# pj9.net
KiCad netlist of a schematic drawn in EAGLE
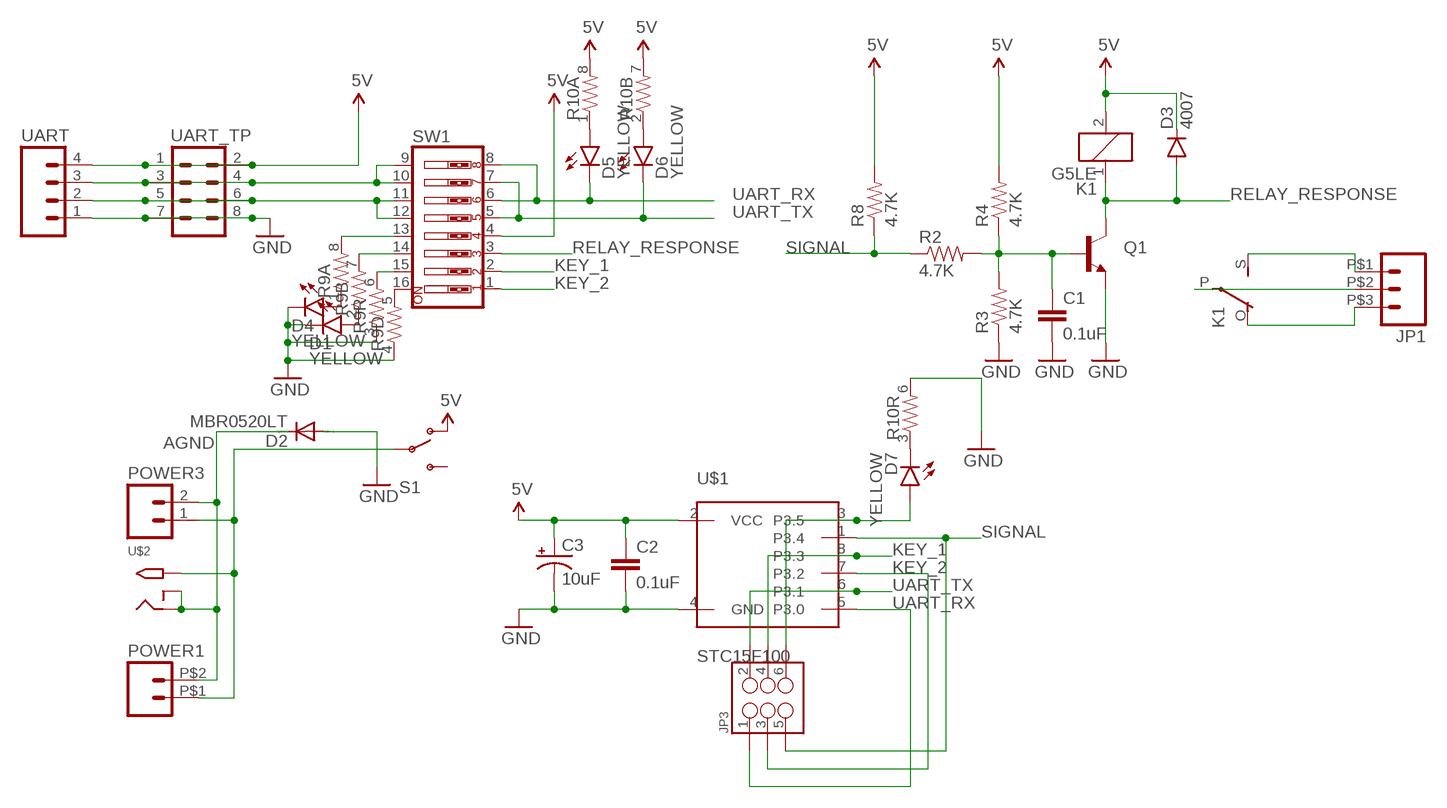
[diagram p0: schematic, sheet 1]

(export (version "E")
  (design (tool "Eeschema 10.0.6"))
  (components
    (comp (ref "C1")
      (value "0.1uF")
      (footprint "eagle-import:0603-CAP")
      (libsource (lib "eagle-import") (part "0.1UF-25V(+80/-20%)(0603)"))
    )
    (comp (ref "C2")
      (value "0.1uF")
      (footprint "eagle-import:0603-CAP")
      (libsource (lib "eagle-import") (part "0.1UF-25V(+80/-20%)(0603)"))
    )
    (comp (ref "C3")
      (value "10uF")
      (footprint "eagle-import:EIA3216")
      (libsource (lib "eagle-import") (part "10UF-16V-10%(TANT)"))
    )
    (comp (ref "D1")
      (value "YELLOW")
      (footprint "eagle-import:LED-1206")
      (libsource (lib "eagle-import") (part "LED-YELLOW1206"))
    )
    (comp (ref "D2")
      (value "MBR0520LT")
      (footprint "eagle-import:SOD123")
      (libsource (lib "eagle-import") (part "MBR0520LT"))
    )
    (comp (ref "D3")
      (value "4007")
      (footprint "eagle-import:SMA-DIODE_ALT")
      (libsource (lib "eagle-import") (part "DIODESMA-ALT"))
    )
    (comp (ref "D4")
      (value "YELLOW")
      (footprint "eagle-import:LED-1206")
      (libsource (lib "eagle-import") (part "LED-YELLOW1206"))
    )
    (comp (ref "D5")
      (value "YELLOW")
      (footprint "eagle-import:LED-1206")
      (libsource (lib "eagle-import") (part "LED-YELLOW1206"))
    )
    (comp (ref "D6")
      (value "YELLOW")
      (footprint "eagle-import:LED-1206")
      (libsource (lib "eagle-import") (part "LED-YELLOW1206"))
    )
    (comp (ref "D7")
      (value "YELLOW")
      (footprint "eagle-import:LED-1206")
      (libsource (lib "eagle-import") (part "LED-YELLOW1206"))
    )
    (comp (ref "JP1")
      (value "M035.08")
      (footprint "eagle-import:1X03_5.08")
      (libsource (lib "eagle-import") (part "M035.08"))
    )
    (comp (ref "JP3")
      (value "M03X2")
      (footprint "eagle-import:2X3_SMD")
      (libsource (lib "eagle-import") (part "M03X2"))
    )
    (comp (ref "K1")
      (value "G5LE")
      (footprint "eagle-import:G5LE")
      (libsource (lib "eagle-import") (part "G5LE"))
    )
    (comp (ref "POWER1")
      (value "M02")
      (footprint "eagle-import:1X02_5.08")
      (libsource (lib "eagle-import") (part "M02"))
    )
    (comp (ref "POWER3")
      (value "M02LOCK")
      (footprint "eagle-import:1X02_LOCK")
      (libsource (lib "eagle-import") (part "M02LOCK"))
    )
    (comp (ref "Q1")
      (value "TRANSISTOR_NPNSOT23-3")
      (footprint "eagle-import:SOT23-3")
      (libsource (lib "eagle-import") (part "TRANSISTOR_NPNSOT23-3"))
    )
    (comp (ref "R2")
      (value "4.7K")
      (footprint "eagle-import:0603-RES")
      (libsource (lib "eagle-import") (part "470OHM1/10W1%(0603)"))
    )
    (comp (ref "R3")
      (value "4.7K")
      (footprint "eagle-import:0603-RES")
      (libsource (lib "eagle-import") (part "470OHM1/10W1%(0603)"))
    )
    (comp (ref "R4")
      (value "4.7K")
      (footprint "eagle-import:0603-RES")
      (libsource (lib "eagle-import") (part "470OHM1/10W1%(0603)"))
    )
    (comp (ref "R8")
      (value "4.7K")
      (footprint "eagle-import:0603-RES")
      (libsource (lib "eagle-import") (part "470OHM1/10W1%(0603)"))
    )
    (comp (ref "R9")
      (value "RESISTOR-ARRAY0603-ARV")
      (footprint "eagle-import:0603-ARV")
      (libsource (lib "eagle-import") (part "RESISTOR-ARRAY0603-ARV"))
    )
    (comp (ref "R10")
      (value "RESISTOR-ARRAY0603-ARV")
      (footprint "eagle-import:0603-ARV")
      (libsource (lib "eagle-import") (part "RESISTOR-ARRAY0603-ARV"))
    )
    (comp (ref "S1")
      (value "SWITCH-SPDTSMD")
      (footprint "eagle-import:AYZ0202")
      (libsource (lib "eagle-import") (part "SWITCH-SPDTSMD"))
    )
    (comp (ref "SW1")
      (value "SW_DIP-8-SMT-HALFSIZE")
      (footprint "eagle-import:DIPSWITCH-08-50MIL")
      (libsource (lib "eagle-import") (part "SW_DIP-8-SMT-HALFSIZE"))
    )
    (comp (ref "U$1")
      (value "STC15F100")
      (footprint "eagle-import:SO08-TIGHT")
      (libsource (lib "eagle-import") (part "STC15F100"))
    )
    (comp (ref "U$2")
      (value "2.1MMJACK")
      (footprint "eagle-import:PJ-102A")
      (libsource (lib "eagle-import") (part "2.1MMJACK"))
    )
    (comp (ref "UART")
      (value "M04LOCK")
      (footprint "eagle-import:1X04_LOCK")
      (libsource (lib "eagle-import") (part "M04LOCK"))
    )
    (comp (ref "UART_TP")
      (value "M04X2SMD")
      (footprint "eagle-import:2X4_SMD")
      (libsource (lib "eagle-import") (part "M04X2SMD"))
    )
  )
  (nets
    (net (code "1") (name "/AGND") (class "Default")
      (node (ref "D2") (pin "C") (pinfunction "C_C") (pintype "passive"))
      (node (ref "POWER1") (pin "P$2") (pinfunction "2_P$2") (pintype "passive"))
      (node (ref "POWER3") (pin "2") (pinfunction "2_2") (pintype "passive"))
      (node (ref "U$2") (pin "RING") (pinfunction "RING_RING") (pintype "bidirectional"))
      (node (ref "U$2") (pin "RING_SW") (pinfunction "RING_SW_RING_SW") (pintype "bidirectional"))
    )
    (net (code "2") (name "/KEY_1") (class "Default")
      (node (ref "JP3") (pin "4") (pinfunction "4_4") (pintype "bidirectional"))
      (node (ref "SW1") (pin "2") (pinfunction "2_2") (pintype "passive"))
      (node (ref "U$1") (pin "8") (pinfunction "P3.3_8") (pintype "bidirectional"))
    )
    (net (code "3") (name "/KEY_2") (class "Default")
      (node (ref "JP3") (pin "3") (pinfunction "3_3") (pintype "bidirectional"))
      (node (ref "SW1") (pin "1") (pinfunction "1_1") (pintype "passive"))
      (node (ref "U$1") (pin "7") (pinfunction "P3.2_7") (pintype "bidirectional"))
    )
    (net (code "4") (name "/RELAY_RESPONSE") (class "Default")
      (node (ref "D3") (pin "A") (pinfunction "A_A") (pintype "passive"))
      (node (ref "K1") (pin "1") (pinfunction "1_1") (pintype "passive"))
      (node (ref "Q1") (pin "3") (pinfunction "C_3") (pintype "passive"))
      (node (ref "SW1") (pin "3") (pinfunction "3_3") (pintype "passive"))
    )
    (net (code "5") (name "/SIGNAL") (class "Default")
      (node (ref "JP3") (pin "5") (pinfunction "5_5") (pintype "bidirectional"))
      (node (ref "R2") (pin "1") (pinfunction "1_1") (pintype "passive"))
      (node (ref "R8") (pin "1") (pinfunction "1_1") (pintype "passive"))
      (node (ref "U$1") (pin "1") (pinfunction "P3.4_1") (pintype "bidirectional"))
    )
    (net (code "6") (name "/UART_RX") (class "Default")
      (node (ref "D5") (pin "C") (pinfunction "C_C") (pintype "passive"))
      (node (ref "JP3") (pin "1") (pinfunction "1_1") (pintype "bidirectional"))
      (node (ref "SW1") (pin "6") (pinfunction "6_6") (pintype "passive"))
      (node (ref "SW1") (pin "8") (pinfunction "8_8") (pintype "passive"))
      (node (ref "U$1") (pin "5") (pinfunction "P3.0_5") (pintype "bidirectional"))
    )
    (net (code "7") (name "/UART_TX") (class "Default")
      (node (ref "D6") (pin "C") (pinfunction "C_C") (pintype "passive"))
      (node (ref "JP3") (pin "2") (pinfunction "2_2") (pintype "bidirectional"))
      (node (ref "SW1") (pin "5") (pinfunction "5_5") (pintype "passive"))
      (node (ref "SW1") (pin "7") (pinfunction "7_7") (pintype "passive"))
      (node (ref "U$1") (pin "6") (pinfunction "P3.1_6") (pintype "bidirectional"))
    )
    (net (code "8") (name "5V") (class "Default")
      (node (ref "C2") (pin "1") (pinfunction "1_1") (pintype "passive"))
      (node (ref "C3") (pin "A") (pinfunction "+_A") (pintype "passive"))
      (node (ref "D3") (pin "C") (pinfunction "C_C") (pintype "passive"))
      (node (ref "K1") (pin "2") (pinfunction "2_2") (pintype "passive"))
      (node (ref "R10") (pin "7") (pinfunction "2_7") (pintype "passive"))
      (node (ref "R10") (pin "8") (pinfunction "2_8") (pintype "passive"))
      (node (ref "R4") (pin "2") (pinfunction "2_2") (pintype "passive"))
      (node (ref "R8") (pin "2") (pinfunction "2_2") (pintype "passive"))
      (node (ref "S1") (pin "1") (pinfunction "O_1") (pintype "passive"))
      (node (ref "SW1") (pin "4") (pinfunction "4_4") (pintype "passive"))
      (node (ref "U$1") (pin "2") (pinfunction "VCC_2") (pintype "bidirectional"))
      (node (ref "UART") (pin "4") (pinfunction "4_4") (pintype "passive"))
      (node (ref "UART_TP") (pin "1") (pinfunction "1_1") (pintype "passive"))
      (node (ref "UART_TP") (pin "2") (pinfunction "2_2") (pintype "passive"))
    )
    (net (code "9") (name "GND") (class "Default")
      (node (ref "C1") (pin "2") (pinfunction "2_2") (pintype "passive"))
      (node (ref "C2") (pin "2") (pinfunction "2_2") (pintype "passive"))
      (node (ref "C3") (pin "C") (pinfunction "-_C") (pintype "passive"))
      (node (ref "D1") (pin "C") (pinfunction "C_C") (pintype "passive"))
      (node (ref "D2") (pin "A") (pinfunction "A_A") (pintype "passive"))
      (node (ref "D4") (pin "C") (pinfunction "C_C") (pintype "passive"))
      (node (ref "Q1") (pin "2") (pinfunction "E_2") (pintype "passive"))
      (node (ref "R10") (pin "6") (pinfunction "2_6") (pintype "passive"))
      (node (ref "R3") (pin "1") (pinfunction "1_1") (pintype "passive"))
      (node (ref "R9") (pin "3") (pinfunction "1_3") (pintype "passive"))
      (node (ref "R9") (pin "4") (pinfunction "1_4") (pintype "passive"))
      (node (ref "U$1") (pin "4") (pinfunction "GND_4") (pintype "bidirectional"))
      (node (ref "UART") (pin "1") (pinfunction "1_1") (pintype "passive"))
      (node (ref "UART_TP") (pin "7") (pinfunction "7_7") (pintype "passive"))
      (node (ref "UART_TP") (pin "8") (pinfunction "8_8") (pintype "passive"))
    )
    (net (code "10") (name "Net-(D4-PadA)") (class "Default")
      (node (ref "D4") (pin "A") (pinfunction "A_A") (pintype "passive"))
      (node (ref "R9") (pin "1") (pinfunction "1_1") (pintype "passive"))
    )
    (net (code "11") (name "Net-(D5-PadA)") (class "Default")
      (node (ref "D5") (pin "A") (pinfunction "A_A") (pintype "passive"))
      (node (ref "R10") (pin "1") (pinfunction "1_1") (pintype "passive"))
    )
    (net (code "12") (name "Net-(JP1-1)") (class "Default")
      (node (ref "JP1") (pin "P$1") (pinfunction "1_P$1") (pintype "passive"))
      (node (ref "K1") (pin "S") (pinfunction "S_S") (pintype "passive"))
    )
    (net (code "13") (name "Net-(JP1-2)") (class "Default")
      (node (ref "JP1") (pin "P$2") (pinfunction "2_P$2") (pintype "passive"))
      (node (ref "K1") (pin "P") (pinfunction "P_P") (pintype "passive"))
    )
    (net (code "14") (name "Net-(JP1-3)") (class "Default")
      (node (ref "JP1") (pin "P$3") (pinfunction "3_P$3") (pintype "passive"))
      (node (ref "K1") (pin "O") (pinfunction "O_O") (pintype "passive"))
    )
    (net (code "15") (name "Net-(POWER1-1)") (class "Default")
      (node (ref "POWER1") (pin "P$1") (pinfunction "1_P$1") (pintype "passive"))
      (node (ref "POWER3") (pin "1") (pinfunction "1_1") (pintype "passive"))
      (node (ref "S1") (pin "2") (pinfunction "P_2") (pintype "passive"))
      (node (ref "U$2") (pin "TIP") (pinfunction "TIP_TIP") (pintype "bidirectional"))
    )
    (net (code "16") (name "Net-(Q1-B)") (class "Default")
      (node (ref "C1") (pin "1") (pinfunction "1_1") (pintype "passive"))
      (node (ref "Q1") (pin "1") (pinfunction "B_1") (pintype "passive"))
      (node (ref "R2") (pin "2") (pinfunction "2_2") (pintype "passive"))
      (node (ref "R3") (pin "2") (pinfunction "2_2") (pintype "passive"))
      (node (ref "R4") (pin "1") (pinfunction "1_1") (pintype "passive"))
    )
    (net (code "17") (name "Net-(R9A-2)") (class "Default")
      (node (ref "R9") (pin "8") (pinfunction "2_8") (pintype "passive"))
      (node (ref "SW1") (pin "13") (pinfunction "13_13") (pintype "passive"))
    )
    (net (code "18") (name "Net-(R9B-1)") (class "Default")
      (node (ref "D1") (pin "A") (pinfunction "A_A") (pintype "passive"))
      (node (ref "R9") (pin "2") (pinfunction "1_2") (pintype "passive"))
    )
    (net (code "19") (name "Net-(R9B-2)") (class "Default")
      (node (ref "R9") (pin "7") (pinfunction "2_7") (pintype "passive"))
      (node (ref "SW1") (pin "14") (pinfunction "14_14") (pintype "passive"))
    )
    (net (code "20") (name "Net-(R9C-2)") (class "Default")
      (node (ref "R9") (pin "5") (pinfunction "2_5") (pintype "passive"))
      (node (ref "SW1") (pin "16") (pinfunction "16_16") (pintype "passive"))
    )
    (net (code "21") (name "Net-(R9D-2)") (class "Default")
      (node (ref "R9") (pin "6") (pinfunction "2_6") (pintype "passive"))
      (node (ref "SW1") (pin "15") (pinfunction "15_15") (pintype "passive"))
    )
    (net (code "22") (name "Net-(R10B-1)") (class "Default")
      (node (ref "D6") (pin "A") (pinfunction "A_A") (pintype "passive"))
      (node (ref "R10") (pin "2") (pinfunction "1_2") (pintype "passive"))
    )
    (net (code "23") (name "Net-(R10D-1)") (class "Default")
      (node (ref "D7") (pin "C") (pinfunction "C_C") (pintype "passive"))
      (node (ref "R10") (pin "3") (pinfunction "1_3") (pintype "passive"))
    )
    (net (code "24") (name "Net-(SW1-Pad10)") (class "Default")
      (node (ref "SW1") (pin "10") (pinfunction "10_10") (pintype "passive"))
      (node (ref "SW1") (pin "9") (pinfunction "9_9") (pintype "passive"))
      (node (ref "UART") (pin "3") (pinfunction "3_3") (pintype "passive"))
      (node (ref "UART_TP") (pin "3") (pinfunction "3_3") (pintype "passive"))
      (node (ref "UART_TP") (pin "4") (pinfunction "4_4") (pintype "passive"))
    )
    (net (code "25") (name "Net-(SW1-Pad11)") (class "Default")
      (node (ref "SW1") (pin "11") (pinfunction "11_11") (pintype "passive"))
      (node (ref "SW1") (pin "12") (pinfunction "12_12") (pintype "passive"))
      (node (ref "UART") (pin "2") (pinfunction "2_2") (pintype "passive"))
      (node (ref "UART_TP") (pin "5") (pinfunction "5_5") (pintype "passive"))
      (node (ref "UART_TP") (pin "6") (pinfunction "6_6") (pintype "passive"))
    )
    (net (code "26") (name "Net-(U$1-P3.5)") (class "Default")
      (node (ref "D7") (pin "A") (pinfunction "A_A") (pintype "passive"))
      (node (ref "JP3") (pin "6") (pinfunction "6_6") (pintype "bidirectional"))
      (node (ref "U$1") (pin "3") (pinfunction "P3.5_3") (pintype "bidirectional"))
    )
    (net (code "27") (name "unconnected-(S1-S-Pad3)") (class "Default")
      (node (ref "S1") (pin "3") (pinfunction "S_3") (pintype "passive"))
    )
  )
)
